# Sata_Drives2.net
KiCad netlist of a schematic drawn in Altium Designer
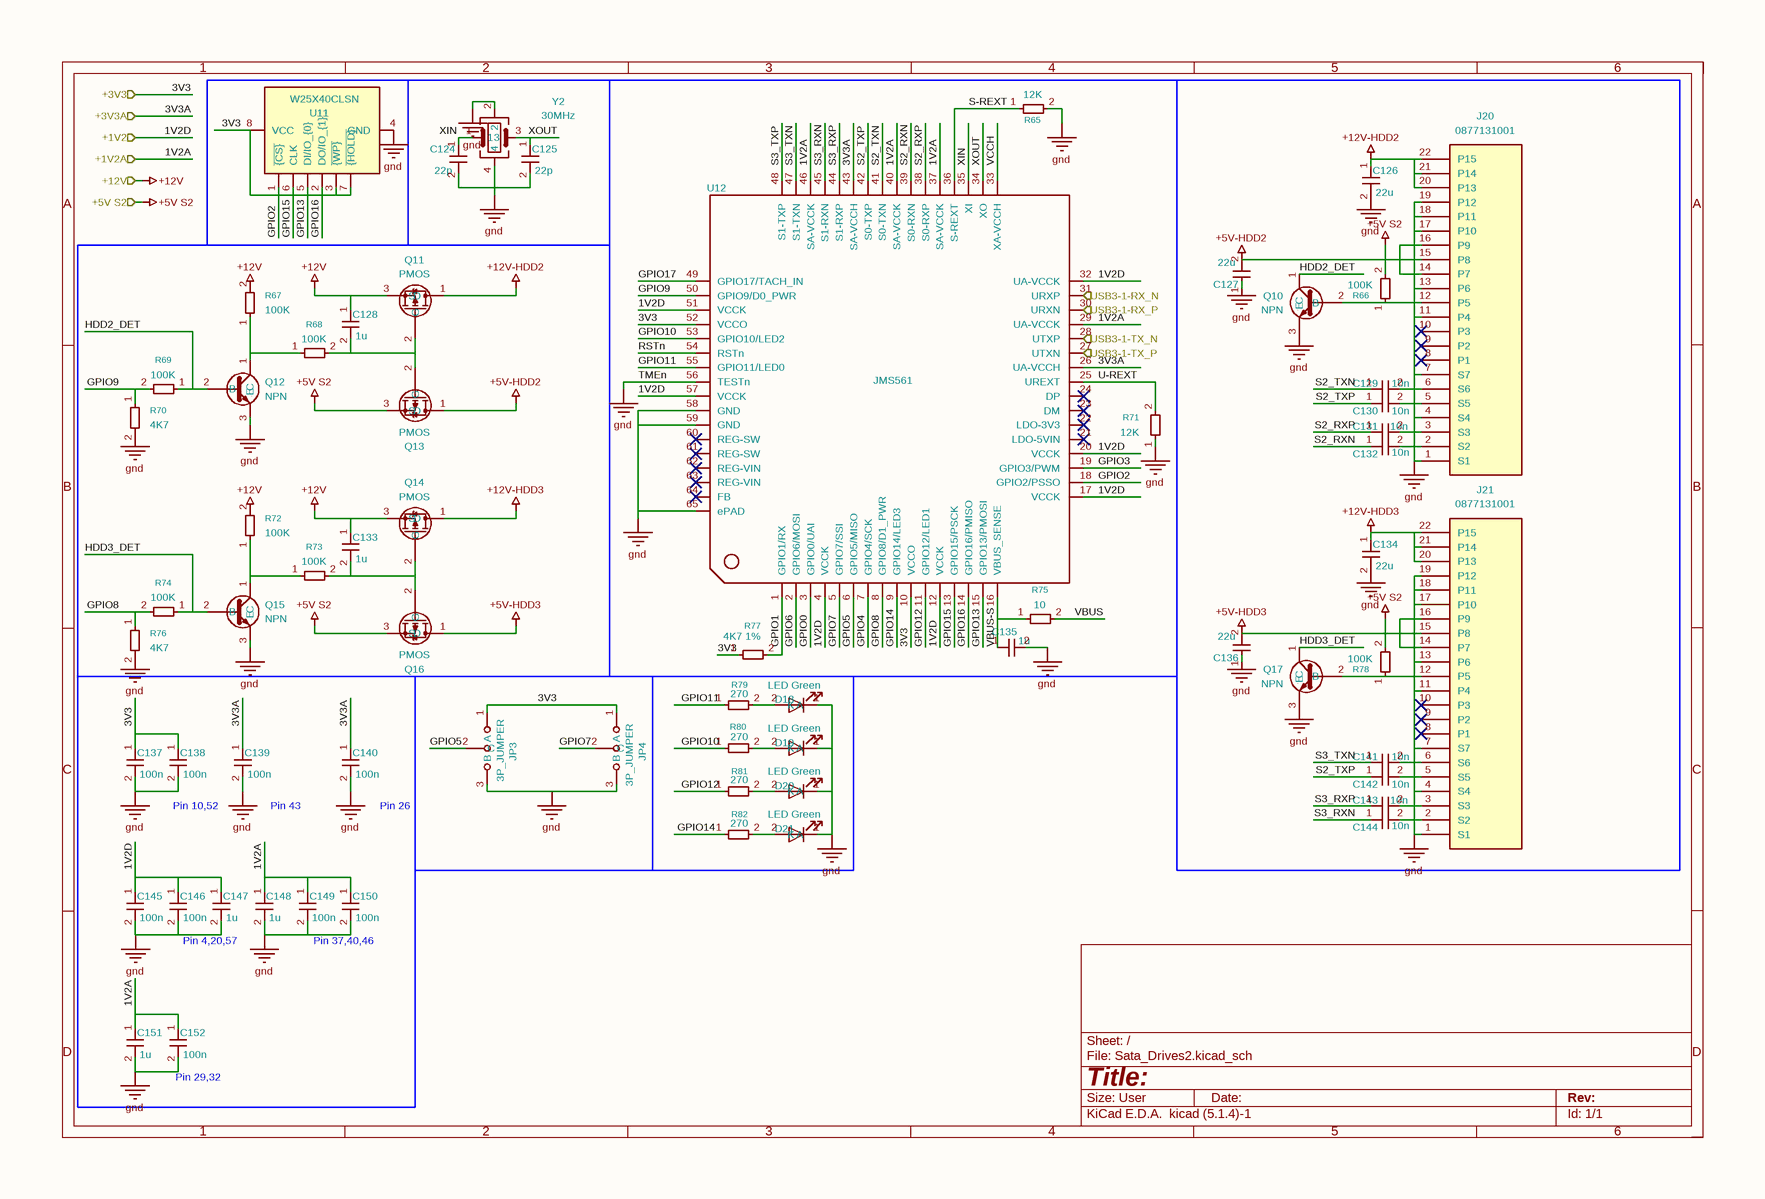
[diagram p0: Sata_Drives2.SchDoc]

(export (version "E")
  (design (tool "Eeschema 10.0.6"))
  (components
    (comp (ref "C124")
      (value "22p")
      (description "Unpolarized capacitor, small symbol")
      (libsource (lib "Device") (part "C_Small"))
    )
    (comp (ref "C125")
      (value "22p")
      (description "Unpolarized capacitor, small symbol")
      (libsource (lib "Device") (part "C_Small"))
    )
    (comp (ref "C126")
      (value "22u")
      (description "Unpolarized capacitor, small symbol")
      (libsource (lib "Device") (part "C_Small"))
    )
    (comp (ref "C127")
      (value "22u")
      (description "Unpolarized capacitor, small symbol")
      (libsource (lib "Device") (part "C_Small"))
    )
    (comp (ref "C128")
      (value "1u")
      (description "Unpolarized capacitor, small symbol")
      (libsource (lib "Device") (part "C_Small"))
    )
    (comp (ref "C129")
      (value "10n")
      (description "Unpolarized capacitor, small symbol")
      (libsource (lib "Device") (part "C_Small"))
    )
    (comp (ref "C130")
      (value "10n")
      (description "Unpolarized capacitor, small symbol")
      (libsource (lib "Device") (part "C_Small"))
    )
    (comp (ref "C131")
      (value "10n")
      (description "Unpolarized capacitor, small symbol")
      (libsource (lib "Device") (part "C_Small"))
    )
    (comp (ref "C132")
      (value "10n")
      (description "Unpolarized capacitor, small symbol")
      (libsource (lib "Device") (part "C_Small"))
    )
    (comp (ref "C133")
      (value "1u")
      (description "Unpolarized capacitor, small symbol")
      (libsource (lib "Device") (part "C_Small"))
    )
    (comp (ref "C134")
      (value "22u")
      (description "Unpolarized capacitor, small symbol")
      (libsource (lib "Device") (part "C_Small"))
    )
    (comp (ref "C135")
      (value "1u")
      (description "Unpolarized capacitor, small symbol")
      (libsource (lib "Device") (part "C_Small"))
    )
    (comp (ref "C136")
      (value "22u")
      (description "Unpolarized capacitor, small symbol")
      (libsource (lib "Device") (part "C_Small"))
    )
    (comp (ref "C137")
      (value "100n")
      (description "Unpolarized capacitor, small symbol")
      (libsource (lib "Device") (part "C_Small"))
    )
    (comp (ref "C138")
      (value "100n")
      (description "Unpolarized capacitor, small symbol")
      (libsource (lib "Device") (part "C_Small"))
    )
    (comp (ref "C139")
      (value "100n")
      (description "Unpolarized capacitor, small symbol")
      (libsource (lib "Device") (part "C_Small"))
    )
    (comp (ref "C140")
      (value "100n")
      (description "Unpolarized capacitor, small symbol")
      (libsource (lib "Device") (part "C_Small"))
    )
    (comp (ref "C141")
      (value "10n")
      (description "Unpolarized capacitor, small symbol")
      (libsource (lib "Device") (part "C_Small"))
    )
    (comp (ref "C142")
      (value "10n")
      (description "Unpolarized capacitor, small symbol")
      (libsource (lib "Device") (part "C_Small"))
    )
    (comp (ref "C143")
      (value "10n")
      (description "Unpolarized capacitor, small symbol")
      (libsource (lib "Device") (part "C_Small"))
    )
    (comp (ref "C144")
      (value "10n")
      (description "Unpolarized capacitor, small symbol")
      (libsource (lib "Device") (part "C_Small"))
    )
    (comp (ref "C145")
      (value "100n")
      (description "Unpolarized capacitor, small symbol")
      (libsource (lib "Device") (part "C_Small"))
    )
    (comp (ref "C146")
      (value "100n")
      (description "Unpolarized capacitor, small symbol")
      (libsource (lib "Device") (part "C_Small"))
    )
    (comp (ref "C147")
      (value "1u")
      (description "Unpolarized capacitor, small symbol")
      (libsource (lib "Device") (part "C_Small"))
    )
    (comp (ref "C148")
      (value "1u")
      (description "Unpolarized capacitor, small symbol")
      (libsource (lib "Device") (part "C_Small"))
    )
    (comp (ref "C149")
      (value "100n")
      (description "Unpolarized capacitor, small symbol")
      (libsource (lib "Device") (part "C_Small"))
    )
    (comp (ref "C150")
      (value "100n")
      (description "Unpolarized capacitor, small symbol")
      (libsource (lib "Device") (part "C_Small"))
    )
    (comp (ref "C151")
      (value "1u")
      (description "Unpolarized capacitor, small symbol")
      (libsource (lib "Device") (part "C_Small"))
    )
    (comp (ref "C152")
      (value "100n")
      (description "Unpolarized capacitor, small symbol")
      (libsource (lib "Device") (part "C_Small"))
    )
    (comp (ref "D18") (value "LED Green") (libsource (lib "Device") (part "LED")))
    (comp (ref "D19") (value "LED Green") (libsource (lib "Device") (part "LED")))
    (comp (ref "D20") (value "LED Green") (libsource (lib "Device") (part "LED")))
    (comp (ref "D21") (value "LED Green") (libsource (lib "Device") (part "LED")))
    (comp (ref "J20")
      (value "0877131001")
      (description "CONN RCPT 22POS STR .05\" SMD AU")
      (libsource (lib "0877131001") (part "0877131001"))
    )
    (comp (ref "J21")
      (value "0877131001")
      (description "CONN RCPT 22POS STR .05\" SMD AU")
      (libsource (lib "0877131001") (part "0877131001"))
    )
    (comp (ref "JP3")
      (value "3P_JUMPER")
      (description "Jumper, 3-pole, pins 1+2 closed/bridged")
      (libsource (lib "Jumper") (part "Jumper_3_Bridged12"))
    )
    (comp (ref "JP4")
      (value "3P_JUMPER")
      (description "Jumper, 3-pole, pins 1+2 closed/bridged")
      (libsource (lib "Jumper") (part "Jumper_3_Bridged12"))
    )
    (comp (ref "Q10")
      (value "NPN")
      (description "Bipolar transistor symbol for simulation only, substrate tied to the emitter")
      (libsource (lib "Simulation_SPICE") (part "NPN"))
    )
    (comp (ref "Q11")
      (value "PMOS")
      (description "P-MOSFET transistor, drain/source/gate")
      (libsource (lib "Simulation_SPICE") (part "PMOS"))
    )
    (comp (ref "Q12")
      (value "NPN")
      (description "Bipolar transistor symbol for simulation only, substrate tied to the emitter")
      (libsource (lib "Simulation_SPICE") (part "NPN"))
    )
    (comp (ref "Q13")
      (value "PMOS")
      (description "P-MOSFET transistor, drain/source/gate")
      (libsource (lib "Simulation_SPICE") (part "PMOS"))
    )
    (comp (ref "Q14")
      (value "PMOS")
      (description "P-MOSFET transistor, drain/source/gate")
      (libsource (lib "Simulation_SPICE") (part "PMOS"))
    )
    (comp (ref "Q15")
      (value "NPN")
      (description "Bipolar transistor symbol for simulation only, substrate tied to the emitter")
      (libsource (lib "Simulation_SPICE") (part "NPN"))
    )
    (comp (ref "Q16")
      (value "PMOS")
      (description "P-MOSFET transistor, drain/source/gate")
      (libsource (lib "Simulation_SPICE") (part "PMOS"))
    )
    (comp (ref "Q17")
      (value "NPN")
      (description "Bipolar transistor symbol for simulation only, substrate tied to the emitter")
      (libsource (lib "Simulation_SPICE") (part "NPN"))
    )
    (comp (ref "R65")
      (value "12K")
      (description "Resistor, small symbol")
      (libsource (lib "Device") (part "R_Small"))
    )
    (comp (ref "R66")
      (value "100K")
      (description "Resistor, small symbol")
      (libsource (lib "") (part "R_Small_2"))
    )
    (comp (ref "R67")
      (value "100K")
      (description "Resistor, small symbol")
      (libsource (lib "") (part "R_Small_2"))
    )
    (comp (ref "R68")
      (value "100K")
      (description "Resistor, small symbol")
      (libsource (lib "Device") (part "R_Small"))
    )
    (comp (ref "R69")
      (value "100K")
      (description "Resistor, small symbol")
      (libsource (lib "") (part "R_Small_1"))
    )
    (comp (ref "R70")
      (value "4K7")
      (description "Resistor, small symbol")
      (libsource (lib "") (part "R_Small_3"))
    )
    (comp (ref "R71")
      (value "12K")
      (description "Resistor, small symbol")
      (libsource (lib "Device") (part "R_Small"))
    )
    (comp (ref "R72")
      (value "100K")
      (description "Resistor, small symbol")
      (libsource (lib "") (part "R_Small_2"))
    )
    (comp (ref "R73")
      (value "100K")
      (description "Resistor, small symbol")
      (libsource (lib "Device") (part "R_Small"))
    )
    (comp (ref "R74")
      (value "100K")
      (description "Resistor, small symbol")
      (libsource (lib "") (part "R_Small_1"))
    )
    (comp (ref "R75")
      (value "10")
      (description "Resistor, small symbol")
      (libsource (lib "Device") (part "R_Small"))
    )
    (comp (ref "R76")
      (value "4K7")
      (description "Resistor, small symbol")
      (libsource (lib "") (part "R_Small_3"))
    )
    (comp (ref "R77")
      (value "4K7 1%")
      (description "Resistor, small symbol")
      (libsource (lib "Device") (part "R_Small"))
    )
    (comp (ref "R78")
      (value "100K")
      (description "Resistor, small symbol")
      (libsource (lib "") (part "R_Small_2"))
    )
    (comp (ref "R79")
      (value "270")
      (description "Resistor, small symbol")
      (libsource (lib "Device") (part "R_Small"))
    )
    (comp (ref "R80")
      (value "270")
      (description "Resistor, small symbol")
      (libsource (lib "Device") (part "R_Small"))
    )
    (comp (ref "R81")
      (value "270")
      (description "Resistor, small symbol")
      (libsource (lib "Device") (part "R_Small"))
    )
    (comp (ref "R82")
      (value "270")
      (description "Resistor, small symbol")
      (libsource (lib "Device") (part "R_Small"))
    )
    (comp (ref "U11")
      (value "W25X40CLSN")
      (description "4Mbit / 512KiB Serial Flash memory, Standard/Dual I/O SPI, 2.3-3.6V, SOIC-8 (150 mil)")
      (libsource (lib "Memory_Flash") (part "W25X40CLSN"))
    )
    (comp (ref "U12") (value "JMS561") (libsource (lib "JMS561") (part "JMS561")))
    (comp (ref "Y2")
      (value "30MHz")
      (description "Four pin crystal, GND on pins 2 and 4")
      (libsource (lib "Device") (part "Crystal_GND24"))
    )
  )
  (nets
    (net (code "1") (name "+5V S2") (class "Default")
      (node (ref "Q13") (pin "3") (pinfunction "S_3") (pintype "passive"))
      (node (ref "Q16") (pin "3") (pinfunction "S_3") (pintype "passive"))
      (node (ref "R66") (pin "2") (pinfunction "2_2") (pintype "passive"))
      (node (ref "R78") (pin "2") (pinfunction "2_2") (pintype "passive"))
    )
    (net (code "2") (name "+5V-HDD2") (class "Default")
      (node (ref "C127") (pin "2") (pinfunction "2_2") (pintype "passive"))
      (node (ref "J20") (pin "14") (pinfunction "P7_14") (pintype "passive"))
      (node (ref "J20") (pin "15") (pinfunction "P8_15") (pintype "passive"))
      (node (ref "J20") (pin "16") (pinfunction "P9_16") (pintype "passive"))
      (node (ref "Q13") (pin "1") (pinfunction "D_1") (pintype "passive"))
    )
    (net (code "3") (name "+5V-HDD3") (class "Default")
      (node (ref "C136") (pin "2") (pinfunction "2_2") (pintype "passive"))
      (node (ref "J21") (pin "14") (pinfunction "P7_14") (pintype "passive"))
      (node (ref "J21") (pin "15") (pinfunction "P8_15") (pintype "passive"))
      (node (ref "J21") (pin "16") (pinfunction "P9_16") (pintype "passive"))
      (node (ref "Q16") (pin "1") (pinfunction "D_1") (pintype "passive"))
    )
    (net (code "4") (name "+12V") (class "Default")
      (node (ref "C128") (pin "1") (pinfunction "1_1") (pintype "passive"))
      (node (ref "C133") (pin "1") (pinfunction "1_1") (pintype "passive"))
      (node (ref "Q11") (pin "3") (pinfunction "S_3") (pintype "passive"))
      (node (ref "Q14") (pin "3") (pinfunction "S_3") (pintype "passive"))
      (node (ref "R67") (pin "2") (pinfunction "2_2") (pintype "passive"))
      (node (ref "R72") (pin "2") (pinfunction "2_2") (pintype "passive"))
    )
    (net (code "5") (name "+12V-HDD2") (class "Default")
      (node (ref "C126") (pin "1") (pinfunction "1_1") (pintype "passive"))
      (node (ref "J20") (pin "20") (pinfunction "P13_20") (pintype "passive"))
      (node (ref "J20") (pin "21") (pinfunction "P14_21") (pintype "passive"))
      (node (ref "J20") (pin "22") (pinfunction "P15_22") (pintype "passive"))
      (node (ref "Q11") (pin "1") (pinfunction "D_1") (pintype "passive"))
    )
    (net (code "6") (name "+12V-HDD3") (class "Default")
      (node (ref "C134") (pin "1") (pinfunction "1_1") (pintype "passive"))
      (node (ref "J21") (pin "20") (pinfunction "P13_20") (pintype "passive"))
      (node (ref "J21") (pin "21") (pinfunction "P14_21") (pintype "passive"))
      (node (ref "J21") (pin "22") (pinfunction "P15_22") (pintype "passive"))
      (node (ref "Q14") (pin "1") (pinfunction "D_1") (pintype "passive"))
    )
    (net (code "7") (name "/1V2A") (class "Default")
      (node (ref "C148") (pin "1") (pinfunction "1_1") (pintype "passive"))
      (node (ref "C149") (pin "1") (pinfunction "1_1") (pintype "passive"))
      (node (ref "C150") (pin "1") (pinfunction "1_1") (pintype "passive"))
      (node (ref "C151") (pin "1") (pinfunction "1_1") (pintype "passive"))
      (node (ref "C152") (pin "1") (pinfunction "1_1") (pintype "passive"))
      (node (ref "U12") (pin "29") (pinfunction "UA-VCCK_29") (pintype "passive"))
      (node (ref "U12") (pin "37") (pinfunction "SA-VCCK_37") (pintype "passive"))
      (node (ref "U12") (pin "40") (pinfunction "SA-VCCK_40") (pintype "passive"))
      (node (ref "U12") (pin "46") (pinfunction "SA-VCCK_46") (pintype "passive"))
    )
    (net (code "8") (name "/1V2D") (class "Default")
      (node (ref "C145") (pin "1") (pinfunction "1_1") (pintype "passive"))
      (node (ref "C146") (pin "1") (pinfunction "1_1") (pintype "passive"))
      (node (ref "C147") (pin "1") (pinfunction "1_1") (pintype "passive"))
      (node (ref "U12") (pin "12") (pinfunction "VCCK_12") (pintype "passive"))
      (node (ref "U12") (pin "17") (pinfunction "VCCK_17") (pintype "passive"))
      (node (ref "U12") (pin "20") (pinfunction "VCCK_20") (pintype "passive"))
      (node (ref "U12") (pin "32") (pinfunction "UA-VCCK_32") (pintype "passive"))
      (node (ref "U12") (pin "4") (pinfunction "VCCK_4") (pintype "passive"))
      (node (ref "U12") (pin "51") (pinfunction "VCCK_51") (pintype "passive"))
      (node (ref "U12") (pin "57") (pinfunction "VCCK_57") (pintype "passive"))
    )
    (net (code "9") (name "/3V3") (class "Default")
      (node (ref "C137") (pin "1") (pinfunction "1_1") (pintype "passive"))
      (node (ref "C138") (pin "1") (pinfunction "1_1") (pintype "passive"))
      (node (ref "JP3") (pin "1") (pinfunction "A_1") (pintype "passive"))
      (node (ref "JP4") (pin "1") (pinfunction "A_1") (pintype "passive"))
      (node (ref "R77") (pin "1") (pinfunction "1_1") (pintype "passive"))
      (node (ref "U11") (pin "3") (pinfunction "~{{WP}}_3") (pintype "passive"))
      (node (ref "U11") (pin "7") (pinfunction "~{{HOLD}}_7") (pintype "passive"))
      (node (ref "U11") (pin "8") (pinfunction "VCC_8") (pintype "passive"))
      (node (ref "U12") (pin "10") (pinfunction "VCCO_10") (pintype "passive"))
      (node (ref "U12") (pin "52") (pinfunction "VCCO_52") (pintype "passive"))
    )
    (net (code "10") (name "/3V3A") (class "Default")
      (node (ref "C139") (pin "1") (pinfunction "1_1") (pintype "passive"))
      (node (ref "C140") (pin "1") (pinfunction "1_1") (pintype "passive"))
      (node (ref "U12") (pin "26") (pinfunction "UA-VCCH_26") (pintype "passive"))
      (node (ref "U12") (pin "43") (pinfunction "SA-VCCH_43") (pintype "passive"))
    )
    (net (code "11") (name "/GPIO0") (class "Default")
      (node (ref "U12") (pin "3") (pinfunction "GPIO0/UAI_3") (pintype "passive"))
    )
    (net (code "12") (name "/GPIO1") (class "Default")
      (node (ref "R77") (pin "2") (pinfunction "2_2") (pintype "passive"))
      (node (ref "U12") (pin "1") (pinfunction "GPIO1/RX_1") (pintype "passive"))
    )
    (net (code "13") (name "/GPIO2") (class "Default")
      (node (ref "U11") (pin "1") (pinfunction "~{{CS}}_1") (pintype "passive"))
      (node (ref "U12") (pin "18") (pinfunction "GPIO2/PSSO_18") (pintype "passive"))
    )
    (net (code "14") (name "/GPIO3") (class "Default")
      (node (ref "U12") (pin "19") (pinfunction "GPIO3/PWM_19") (pintype "passive"))
    )
    (net (code "15") (name "/GPIO4") (class "Default")
      (node (ref "U12") (pin "7") (pinfunction "GPIO4/SCK_7") (pintype "passive"))
    )
    (net (code "16") (name "/GPIO5") (class "Default")
      (node (ref "JP3") (pin "2") (pinfunction "C_2") (pintype "passive"))
      (node (ref "U12") (pin "6") (pinfunction "GPIO5/MISO_6") (pintype "passive"))
    )
    (net (code "17") (name "/GPIO6") (class "Default")
      (node (ref "U12") (pin "2") (pinfunction "GPIO6/MOSI_2") (pintype "passive"))
    )
    (net (code "18") (name "/GPIO7") (class "Default")
      (node (ref "JP4") (pin "2") (pinfunction "C_2") (pintype "passive"))
      (node (ref "U12") (pin "5") (pinfunction "GPIO7/SSI_5") (pintype "passive"))
    )
    (net (code "19") (name "/GPIO8") (class "Default")
      (node (ref "R74") (pin "2") (pinfunction "2_2") (pintype "passive"))
      (node (ref "R76") (pin "1") (pinfunction "1_1") (pintype "passive"))
      (node (ref "U12") (pin "8") (pinfunction "GPIO8/D1_PWR_8") (pintype "passive"))
    )
    (net (code "20") (name "/GPIO9") (class "Default")
      (node (ref "R69") (pin "2") (pinfunction "2_2") (pintype "passive"))
      (node (ref "R70") (pin "1") (pinfunction "1_1") (pintype "passive"))
      (node (ref "U12") (pin "50") (pinfunction "GPIO9/D0_PWR_50") (pintype "passive"))
    )
    (net (code "21") (name "/GPIO10") (class "Default")
      (node (ref "R80") (pin "1") (pinfunction "1_1") (pintype "passive"))
      (node (ref "U12") (pin "53") (pinfunction "GPIO10/LED2_53") (pintype "passive"))
    )
    (net (code "22") (name "/GPIO11") (class "Default")
      (node (ref "R79") (pin "1") (pinfunction "1_1") (pintype "passive"))
      (node (ref "U12") (pin "55") (pinfunction "GPIO11/LED0_55") (pintype "passive"))
    )
    (net (code "23") (name "/GPIO12") (class "Default")
      (node (ref "R81") (pin "1") (pinfunction "1_1") (pintype "passive"))
      (node (ref "U12") (pin "11") (pinfunction "GPIO12/LED1_11") (pintype "passive"))
    )
    (net (code "24") (name "/GPIO13") (class "Default")
      (node (ref "U11") (pin "5") (pinfunction "DI/IO_{0}_5") (pintype "passive"))
      (node (ref "U12") (pin "15") (pinfunction "GPIO13/PMOSI_15") (pintype "passive"))
    )
    (net (code "25") (name "/GPIO14") (class "Default")
      (node (ref "R82") (pin "1") (pinfunction "1_1") (pintype "passive"))
      (node (ref "U12") (pin "9") (pinfunction "GPIO14/LED3_9") (pintype "passive"))
    )
    (net (code "26") (name "/GPIO15") (class "Default")
      (node (ref "U11") (pin "6") (pinfunction "CLK_6") (pintype "passive"))
      (node (ref "U12") (pin "13") (pinfunction "GPIO15/PSCK_13") (pintype "passive"))
    )
    (net (code "27") (name "/GPIO16") (class "Default")
      (node (ref "U11") (pin "2") (pinfunction "DO/IO_{1}_2") (pintype "passive"))
      (node (ref "U12") (pin "14") (pinfunction "GPIO16/PMISO_14") (pintype "passive"))
    )
    (net (code "28") (name "/GPIO17") (class "Default")
      (node (ref "U12") (pin "49") (pinfunction "GPIO17/TACH_IN_49") (pintype "passive"))
    )
    (net (code "29") (name "/HDD2_DET") (class "Default")
      (node (ref "Q10") (pin "1") (pinfunction "C_1") (pintype "passive"))
      (node (ref "Q12") (pin "2") (pinfunction "B_2") (pintype "passive"))
      (node (ref "R69") (pin "1") (pinfunction "1_1") (pintype "passive"))
    )
    (net (code "30") (name "/HDD3_DET") (class "Default")
      (node (ref "Q15") (pin "2") (pinfunction "B_2") (pintype "passive"))
      (node (ref "Q17") (pin "1") (pinfunction "C_1") (pintype "passive"))
      (node (ref "R74") (pin "1") (pinfunction "1_1") (pintype "passive"))
    )
    (net (code "31") (name "/RSTn") (class "Default")
      (node (ref "U12") (pin "54") (pinfunction "RSTn_54") (pintype "passive"))
    )
    (net (code "32") (name "/S-REXT") (class "Default")
      (node (ref "R65") (pin "1") (pinfunction "1_1") (pintype "passive"))
      (node (ref "U12") (pin "36") (pinfunction "S-REXT_36") (pintype "passive"))
    )
    (net (code "33") (name "/S2_RXN") (class "Default")
      (node (ref "C132") (pin "1") (pinfunction "1_1") (pintype "passive"))
      (node (ref "U12") (pin "39") (pinfunction "S0-RXN_39") (pintype "passive"))
    )
    (net (code "34") (name "/S2_RXP") (class "Default")
      (node (ref "C131") (pin "1") (pinfunction "1_1") (pintype "passive"))
      (node (ref "U12") (pin "38") (pinfunction "S0-RXP_38") (pintype "passive"))
    )
    (net (code "35") (name "/S2_TXN") (class "Default")
      (node (ref "C129") (pin "1") (pinfunction "1_1") (pintype "passive"))
      (node (ref "U12") (pin "41") (pinfunction "S0-TXN_41") (pintype "passive"))
    )
    (net (code "36") (name "/S2_TXP") (class "Default")
      (node (ref "C130") (pin "1") (pinfunction "1_1") (pintype "passive"))
      (node (ref "C142") (pin "1") (pinfunction "1_1") (pintype "passive"))
      (node (ref "U12") (pin "42") (pinfunction "S0-TXP_42") (pintype "passive"))
    )
    (net (code "37") (name "/S3_RXN") (class "Default")
      (node (ref "C144") (pin "1") (pinfunction "1_1") (pintype "passive"))
      (node (ref "U12") (pin "45") (pinfunction "S1-RXN_45") (pintype "passive"))
    )
    (net (code "38") (name "/S3_RXP") (class "Default")
      (node (ref "C143") (pin "1") (pinfunction "1_1") (pintype "passive"))
      (node (ref "U12") (pin "44") (pinfunction "S1-RXP_44") (pintype "passive"))
    )
    (net (code "39") (name "/S3_TXN") (class "Default")
      (node (ref "C141") (pin "1") (pinfunction "1_1") (pintype "passive"))
      (node (ref "U12") (pin "47") (pinfunction "S1-TXN_47") (pintype "passive"))
    )
    (net (code "40") (name "/S3_TXP") (class "Default")
      (node (ref "U12") (pin "48") (pinfunction "S1-TXP_48") (pintype "passive"))
    )
    (net (code "41") (name "/U-REXT") (class "Default")
      (node (ref "R71") (pin "2") (pinfunction "2_2") (pintype "passive"))
      (node (ref "U12") (pin "25") (pinfunction "UREXT_25") (pintype "passive"))
    )
    (net (code "42") (name "/USB3-1-RX_N") (class "Default")
      (node (ref "U12") (pin "31") (pinfunction "URXP_31") (pintype "passive"))
    )
    (net (code "43") (name "/USB3-1-RX_P") (class "Default")
      (node (ref "U12") (pin "30") (pinfunction "URXN_30") (pintype "passive"))
    )
    (net (code "44") (name "/USB3-1-TX_N") (class "Default")
      (node (ref "U12") (pin "28") (pinfunction "UTXP_28") (pintype "passive"))
    )
    (net (code "45") (name "/USB3-1-TX_P") (class "Default")
      (node (ref "U12") (pin "27") (pinfunction "UTXN_27") (pintype "passive"))
    )
    (net (code "46") (name "/VBUS") (class "Default")
      (node (ref "R75") (pin "2") (pinfunction "2_2") (pintype "passive"))
    )
    (net (code "47") (name "/VBUS-S") (class "Default")
      (node (ref "C135") (pin "1") (pinfunction "1_1") (pintype "passive"))
      (node (ref "R75") (pin "1") (pinfunction "1_1") (pintype "passive"))
      (node (ref "U12") (pin "16") (pinfunction "VBUS_SENSE_16") (pintype "passive"))
    )
    (net (code "48") (name "/VCCH") (class "Default")
      (node (ref "U12") (pin "33") (pinfunction "XA-VCCH_33") (pintype "passive"))
    )
    (net (code "49") (name "/XIN") (class "Default")
      (node (ref "C124") (pin "1") (pinfunction "1_1") (pintype "passive"))
      (node (ref "U12") (pin "35") (pinfunction "XI_35") (pintype "passive"))
      (node (ref "Y2") (pin "1") (pinfunction "1_1") (pintype "passive"))
    )
    (net (code "50") (name "/XOUT") (class "Default")
      (node (ref "C125") (pin "1") (pinfunction "1_1") (pintype "passive"))
      (node (ref "U12") (pin "34") (pinfunction "XO_34") (pintype "passive"))
      (node (ref "Y2") (pin "3") (pinfunction "3_3") (pintype "passive"))
    )
    (net (code "51") (name "Net-(D18-A)") (class "Default")
      (node (ref "D18") (pin "2") (pinfunction "A_2") (pintype "passive"))
      (node (ref "R79") (pin "2") (pinfunction "2_2") (pintype "passive"))
    )
    (net (code "52") (name "Net-(D19-A)") (class "Default")
      (node (ref "D19") (pin "2") (pinfunction "A_2") (pintype "passive"))
      (node (ref "R80") (pin "2") (pinfunction "2_2") (pintype "passive"))
    )
    (net (code "53") (name "Net-(D20-A)") (class "Default")
      (node (ref "D20") (pin "2") (pinfunction "A_2") (pintype "passive"))
      (node (ref "R81") (pin "2") (pinfunction "2_2") (pintype "passive"))
    )
    (net (code "54") (name "Net-(D21-A)") (class "Default")
      (node (ref "D21") (pin "2") (pinfunction "A_2") (pintype "passive"))
      (node (ref "R82") (pin "2") (pinfunction "2_2") (pintype "passive"))
    )
    (net (code "55") (name "Net-(J20-P5)") (class "Default")
      (node (ref "J20") (pin "12") (pinfunction "P5_12") (pintype "passive"))
      (node (ref "Q10") (pin "2") (pinfunction "B_2") (pintype "passive"))
      (node (ref "R66") (pin "1") (pinfunction "1_1") (pintype "passive"))
    )
    (net (code "56") (name "Net-(J20-S2)") (class "Default")
      (node (ref "C132") (pin "2") (pinfunction "2_2") (pintype "passive"))
      (node (ref "J20") (pin "2") (pinfunction "S2_2") (pintype "passive"))
    )
    (net (code "57") (name "Net-(J20-S3)") (class "Default")
      (node (ref "C131") (pin "2") (pinfunction "2_2") (pintype "passive"))
      (node (ref "J20") (pin "3") (pinfunction "S3_3") (pintype "passive"))
    )
    (net (code "58") (name "Net-(J20-S5)") (class "Default")
      (node (ref "C130") (pin "2") (pinfunction "2_2") (pintype "passive"))
      (node (ref "J20") (pin "5") (pinfunction "S5_5") (pintype "passive"))
    )
    (net (code "59") (name "Net-(J20-S6)") (class "Default")
      (node (ref "C129") (pin "2") (pinfunction "2_2") (pintype "passive"))
      (node (ref "J20") (pin "6") (pinfunction "S6_6") (pintype "passive"))
    )
    (net (code "60") (name "Net-(J21-P5)") (class "Default")
      (node (ref "J21") (pin "12") (pinfunction "P5_12") (pintype "passive"))
      (node (ref "Q17") (pin "2") (pinfunction "B_2") (pintype "passive"))
      (node (ref "R78") (pin "1") (pinfunction "1_1") (pintype "passive"))
    )
    (net (code "61") (name "Net-(J21-S2)") (class "Default")
      (node (ref "C144") (pin "2") (pinfunction "2_2") (pintype "passive"))
      (node (ref "J21") (pin "2") (pinfunction "S2_2") (pintype "passive"))
    )
    (net (code "62") (name "Net-(J21-S3)") (class "Default")
      (node (ref "C143") (pin "2") (pinfunction "2_2") (pintype "passive"))
      (node (ref "J21") (pin "3") (pinfunction "S3_3") (pintype "passive"))
    )
    (net (code "63") (name "Net-(J21-S5)") (class "Default")
      (node (ref "C142") (pin "2") (pinfunction "2_2") (pintype "passive"))
      (node (ref "J21") (pin "5") (pinfunction "S5_5") (pintype "passive"))
    )
    (net (code "64") (name "Net-(J21-S6)") (class "Default")
      (node (ref "C141") (pin "2") (pinfunction "2_2") (pintype "passive"))
      (node (ref "J21") (pin "6") (pinfunction "S6_6") (pintype "passive"))
    )
    (net (code "65") (name "Net-(Q11-G)") (class "Default")
      (node (ref "C128") (pin "2") (pinfunction "2_2") (pintype "passive"))
      (node (ref "Q11") (pin "2") (pinfunction "G_2") (pintype "passive"))
      (node (ref "Q13") (pin "2") (pinfunction "G_2") (pintype "passive"))
      (node (ref "R68") (pin "2") (pinfunction "2_2") (pintype "passive"))
    )
    (net (code "66") (name "Net-(Q12-C)") (class "Default")
      (node (ref "Q12") (pin "1") (pinfunction "C_1") (pintype "passive"))
      (node (ref "R67") (pin "1") (pinfunction "1_1") (pintype "passive"))
      (node (ref "R68") (pin "1") (pinfunction "1_1") (pintype "passive"))
    )
    (net (code "67") (name "Net-(Q14-G)") (class "Default")
      (node (ref "C133") (pin "2") (pinfunction "2_2") (pintype "passive"))
      (node (ref "Q14") (pin "2") (pinfunction "G_2") (pintype "passive"))
      (node (ref "Q16") (pin "2") (pinfunction "G_2") (pintype "passive"))
      (node (ref "R73") (pin "2") (pinfunction "2_2") (pintype "passive"))
    )
    (net (code "68") (name "Net-(Q15-C)") (class "Default")
      (node (ref "Q15") (pin "1") (pinfunction "C_1") (pintype "passive"))
      (node (ref "R72") (pin "1") (pinfunction "1_1") (pintype "passive"))
      (node (ref "R73") (pin "1") (pinfunction "1_1") (pintype "passive"))
    )
    (net (code "69") (name "gnd") (class "Default")
      (node (ref "C124") (pin "2") (pinfunction "2_2") (pintype "passive"))
      (node (ref "C125") (pin "2") (pinfunction "2_2") (pintype "passive"))
      (node (ref "C126") (pin "2") (pinfunction "2_2") (pintype "passive"))
      (node (ref "C127") (pin "1") (pinfunction "1_1") (pintype "passive"))
      (node (ref "C134") (pin "2") (pinfunction "2_2") (pintype "passive"))
      (node (ref "C135") (pin "2") (pinfunction "2_2") (pintype "passive"))
      (node (ref "C136") (pin "1") (pinfunction "1_1") (pintype "passive"))
      (node (ref "C137") (pin "2") (pinfunction "2_2") (pintype "passive"))
      (node (ref "C138") (pin "2") (pinfunction "2_2") (pintype "passive"))
      (node (ref "C139") (pin "2") (pinfunction "2_2") (pintype "passive"))
      (node (ref "C140") (pin "2") (pinfunction "2_2") (pintype "passive"))
      (node (ref "C145") (pin "2") (pinfunction "2_2") (pintype "passive"))
      (node (ref "C146") (pin "2") (pinfunction "2_2") (pintype "passive"))
      (node (ref "C147") (pin "2") (pinfunction "2_2") (pintype "passive"))
      (node (ref "C148") (pin "2") (pinfunction "2_2") (pintype "passive"))
      (node (ref "C149") (pin "2") (pinfunction "2_2") (pintype "passive"))
      (node (ref "C150") (pin "2") (pinfunction "2_2") (pintype "passive"))
      (node (ref "C151") (pin "2") (pinfunction "2_2") (pintype "passive"))
      (node (ref "C152") (pin "2") (pinfunction "2_2") (pintype "passive"))
      (node (ref "D18") (pin "1") (pinfunction "K_1") (pintype "passive"))
      (node (ref "D19") (pin "1") (pinfunction "K_1") (pintype "passive"))
      (node (ref "D20") (pin "1") (pinfunction "K_1") (pintype "passive"))
      (node (ref "D21") (pin "1") (pinfunction "K_1") (pintype "passive"))
      (node (ref "J20") (pin "1") (pinfunction "S1_1") (pintype "passive"))
      (node (ref "J20") (pin "11") (pinfunction "P4_11") (pintype "passive"))
      (node (ref "J20") (pin "13") (pinfunction "P6_13") (pintype "passive"))
      (node (ref "J20") (pin "17") (pinfunction "P10_17") (pintype "passive"))
      (node (ref "J20") (pin "18") (pinfunction "P11_18") (pintype "passive"))
      (node (ref "J20") (pin "19") (pinfunction "P12_19") (pintype "passive"))
      (node (ref "J20") (pin "4") (pinfunction "S4_4") (pintype "passive"))
      (node (ref "J20") (pin "7") (pinfunction "S7_7") (pintype "passive"))
      (node (ref "J21") (pin "1") (pinfunction "S1_1") (pintype "passive"))
      (node (ref "J21") (pin "11") (pinfunction "P4_11") (pintype "passive"))
      (node (ref "J21") (pin "13") (pinfunction "P6_13") (pintype "passive"))
      (node (ref "J21") (pin "17") (pinfunction "P10_17") (pintype "passive"))
      (node (ref "J21") (pin "18") (pinfunction "P11_18") (pintype "passive"))
      (node (ref "J21") (pin "19") (pinfunction "P12_19") (pintype "passive"))
      (node (ref "J21") (pin "4") (pinfunction "S4_4") (pintype "passive"))
      (node (ref "J21") (pin "7") (pinfunction "S7_7") (pintype "passive"))
      (node (ref "JP3") (pin "3") (pinfunction "B_3") (pintype "passive"))
      (node (ref "JP4") (pin "3") (pinfunction "B_3") (pintype "passive"))
      (node (ref "Q10") (pin "3") (pinfunction "E_3") (pintype "passive"))
      (node (ref "Q12") (pin "3") (pinfunction "E_3") (pintype "passive"))
      (node (ref "Q15") (pin "3") (pinfunction "E_3") (pintype "passive"))
      (node (ref "Q17") (pin "3") (pinfunction "E_3") (pintype "passive"))
      (node (ref "R65") (pin "2") (pinfunction "2_2") (pintype "passive"))
      (node (ref "R70") (pin "2") (pinfunction "2_2") (pintype "passive"))
      (node (ref "R71") (pin "1") (pinfunction "1_1") (pintype "passive"))
      (node (ref "R76") (pin "2") (pinfunction "2_2") (pintype "passive"))
      (node (ref "U11") (pin "4") (pinfunction "GND_4") (pintype "passive"))
      (node (ref "U12") (pin "56") (pinfunction "TESTn_56") (pintype "passive"))
      (node (ref "U12") (pin "58") (pinfunction "GND_58") (pintype "passive"))
      (node (ref "U12") (pin "59") (pinfunction "GND_59") (pintype "passive"))
      (node (ref "U12") (pin "65") (pinfunction "ePAD_65") (pintype "passive"))
      (node (ref "Y2") (pin "2") (pinfunction "2_2") (pintype "passive"))
      (node (ref "Y2") (pin "4") (pinfunction "4_4") (pintype "passive"))
    )
    (net (code "70") (name "unconnected-(J20-P1-Pad8)") (class "Default")
      (node (ref "J20") (pin "8") (pinfunction "P1_8") (pintype "passive+no_connect"))
    )
    (net (code "71") (name "unconnected-(J20-P2-Pad9)") (class "Default")
      (node (ref "J20") (pin "9") (pinfunction "P2_9") (pintype "passive+no_connect"))
    )
    (net (code "72") (name "unconnected-(J20-P3-Pad10)") (class "Default")
      (node (ref "J20") (pin "10") (pinfunction "P3_10") (pintype "passive+no_connect"))
    )
    (net (code "73") (name "unconnected-(J21-P1-Pad8)") (class "Default")
      (node (ref "J21") (pin "8") (pinfunction "P1_8") (pintype "passive+no_connect"))
    )
    (net (code "74") (name "unconnected-(J21-P2-Pad9)") (class "Default")
      (node (ref "J21") (pin "9") (pinfunction "P2_9") (pintype "passive+no_connect"))
    )
    (net (code "75") (name "unconnected-(J21-P3-Pad10)") (class "Default")
      (node (ref "J21") (pin "10") (pinfunction "P3_10") (pintype "passive+no_connect"))
    )
    (net (code "76") (name "unconnected-(U12-DM-Pad23)") (class "Default")
      (node (ref "U12") (pin "23") (pinfunction "DM_23") (pintype "passive+no_connect"))
    )
    (net (code "77") (name "unconnected-(U12-DP-Pad24)") (class "Default")
      (node (ref "U12") (pin "24") (pinfunction "DP_24") (pintype "passive+no_connect"))
    )
    (net (code "78") (name "unconnected-(U12-FB-Pad64)") (class "Default")
      (node (ref "U12") (pin "64") (pinfunction "FB_64") (pintype "passive+no_connect"))
    )
    (net (code "79") (name "unconnected-(U12-LDO-3V3-Pad22)") (class "Default")
      (node (ref "U12") (pin "22") (pinfunction "LDO-3V3_22") (pintype "passive+no_connect"))
    )
    (net (code "80") (name "unconnected-(U12-LDO-5VIN-Pad21)") (class "Default")
      (node (ref "U12") (pin "21") (pinfunction "LDO-5VIN_21") (pintype "passive+no_connect"))
    )
    (net (code "81") (name "unconnected-(U12-REG-SW-Pad60)") (class "Default")
      (node (ref "U12") (pin "60") (pinfunction "REG-SW_60") (pintype "passive+no_connect"))
    )
    (net (code "82") (name "unconnected-(U12-REG-SW-Pad61)") (class "Default")
      (node (ref "U12") (pin "61") (pinfunction "REG-SW_61") (pintype "passive+no_connect"))
    )
    (net (code "83") (name "unconnected-(U12-REG-VIN-Pad62)") (class "Default")
      (node (ref "U12") (pin "62") (pinfunction "REG-VIN_62") (pintype "passive+no_connect"))
    )
    (net (code "84") (name "unconnected-(U12-REG-VIN-Pad63)") (class "Default")
      (node (ref "U12") (pin "63") (pinfunction "REG-VIN_63") (pintype "passive+no_connect"))
    )
  )
)
